# SFP.net
KiCad netlist of a schematic drawn in Altium Designer
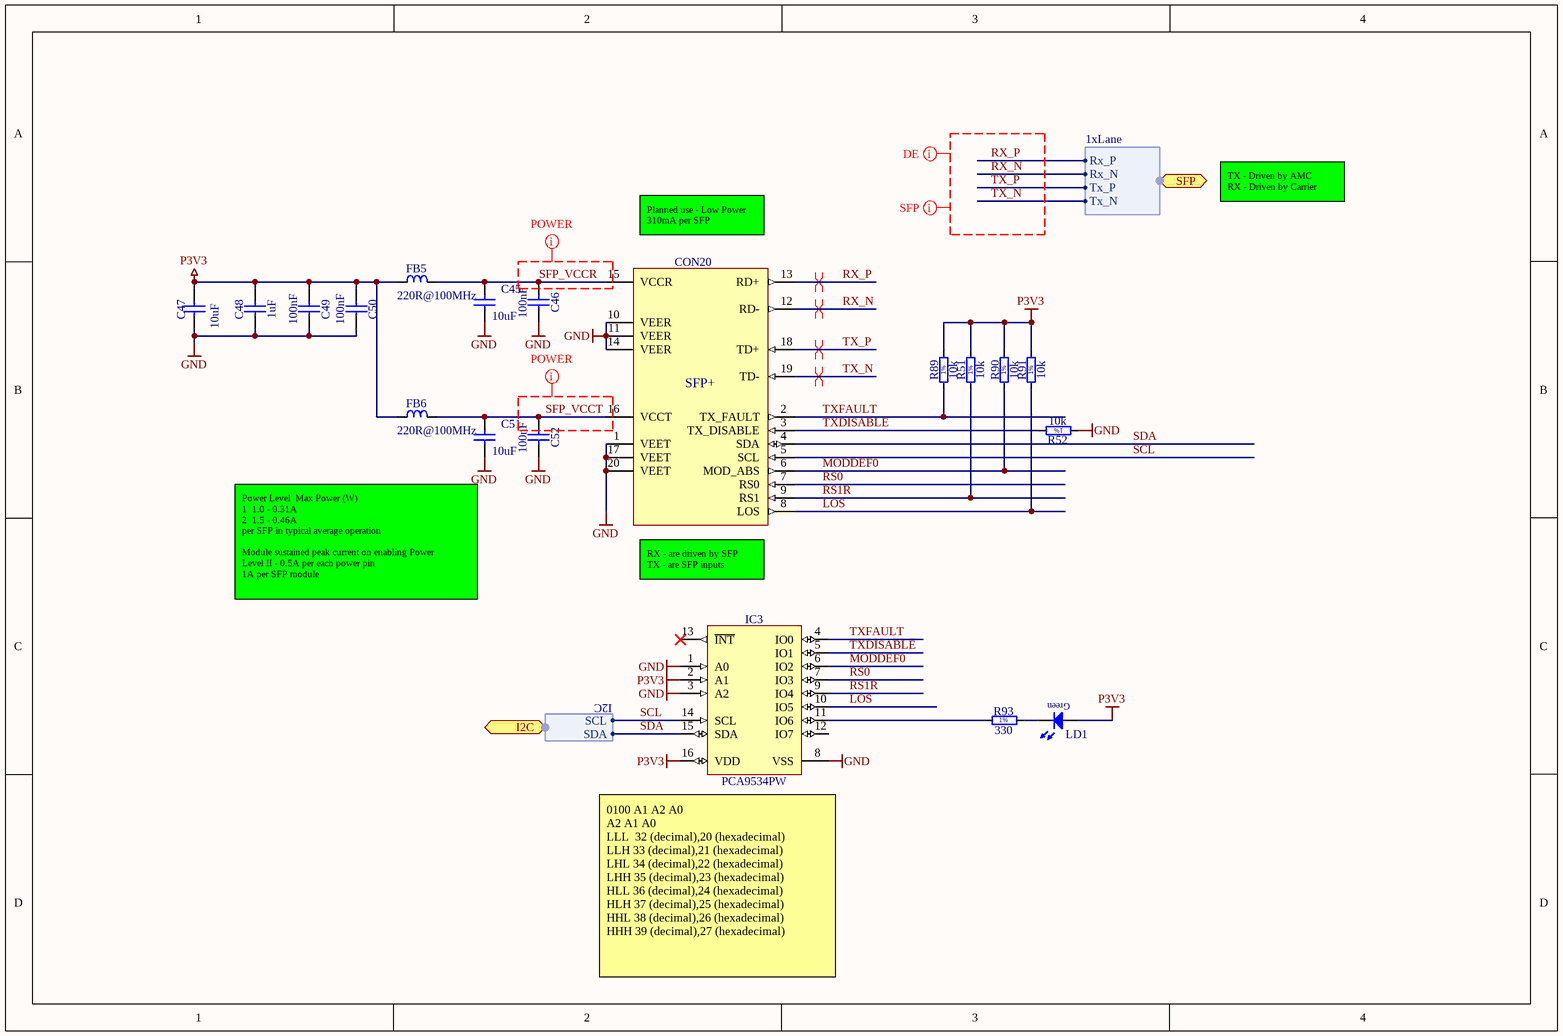
[diagram p0: SFP.SchDoc]

(export (version "E")
  (design (tool "Eeschema 10.0.6"))
  (components
    (comp (ref "C45")
      (value "10uF")
      (footprint "CAPC2012X135N")
      (description "Non-polarised capacitor")
      (fields
        (field (name "PART NUMBER") "CC0805_10UF_10V_10%_X7R")
        (field (name "VOLTAGE") "10V")
        (field (name "AUTHOR") "CERN DEM JLC")
      )
      (libsource (lib "Capacitors") (part "Capacitor - non polarized"))
    )
    (comp (ref "C46")
      (value "100nF")
      (footprint "CAPC1005X55N")
      (description "Non-polarised capacitor")
      (fields
        (field (name "PART NUMBER") "CC0402_100NF_16V_10%_X5R")
        (field (name "VOLTAGE") "16V")
        (field (name "AUTHOR") "CERN DEM JLC")
      )
      (libsource (lib "Capacitors") (part "Capacitor - non polarized"))
    )
    (comp (ref "C47")
      (value "10uF")
      (footprint "CAPC2012X135N")
      (description "Non-polarised capacitor")
      (fields
        (field (name "PART NUMBER") "CC0805_10UF_10V_10%_X7R")
        (field (name "VOLTAGE") "10V")
        (field (name "AUTHOR") "CERN DEM JLC")
      )
      (libsource (lib "Capacitors") (part "Capacitor - non polarized"))
    )
    (comp (ref "C48")
      (value "1uF")
      (footprint "CAPC1608X87N")
      (description "Non-polarised capacitor")
      (fields
        (field (name "PART NUMBER") "CC0603_1UF_25V_10%_X7R")
        (field (name "VOLTAGE") "25V")
        (field (name "AUTHOR") "CERN DEM JLC")
      )
      (libsource (lib "Capacitors") (part "Capacitor - non polarized"))
    )
    (comp (ref "C49")
      (value "100nF")
      (footprint "CAPC1005X55N")
      (description "Non-polarised capacitor")
      (fields
        (field (name "PART NUMBER") "CC0402_100NF_16V_10%_X5R")
        (field (name "VOLTAGE") "16V")
        (field (name "AUTHOR") "CERN DEM JLC")
      )
      (libsource (lib "Capacitors") (part "Capacitor - non polarized"))
    )
    (comp (ref "C50")
      (value "100nF")
      (footprint "CAPC1005X55N")
      (description "Non-polarised capacitor")
      (fields
        (field (name "PART NUMBER") "CC0402_100NF_16V_10%_X5R")
        (field (name "VOLTAGE") "16V")
        (field (name "AUTHOR") "CERN DEM JLC")
      )
      (libsource (lib "Capacitors") (part "Capacitor - non polarized"))
    )
    (comp (ref "C51")
      (value "10uF")
      (footprint "CAPC2012X135N")
      (description "Non-polarised capacitor")
      (fields
        (field (name "PART NUMBER") "CC0805_10UF_10V_10%_X7R")
        (field (name "VOLTAGE") "10V")
        (field (name "AUTHOR") "CERN DEM JLC")
      )
      (libsource (lib "Capacitors") (part "Capacitor - non polarized"))
    )
    (comp (ref "C52")
      (value "100nF")
      (footprint "CAPC1005X55N")
      (description "Non-polarised capacitor")
      (fields
        (field (name "PART NUMBER") "CC0402_100NF_16V_10%_X5R")
        (field (name "VOLTAGE") "16V")
        (field (name "AUTHOR") "CERN DEM JLC")
      )
      (libsource (lib "Capacitors") (part "Capacitor - non polarized"))
    )
    (comp (ref "CON20")
      (value "1888247-1")
      (footprint "TYCO_1888247-1")
      (description "20 Position SFP+ Connector (Small Form-factor Pluggable)")
      (fields
        (field (name "PART NUMBER") "TYCO_1888247-1")
        (field (name "MANUFACTURER") "TYCO ELECTRONICS")
        (field (name "AUTHOR") "CERN DEM JLC")
      )
      (libsource (lib "Connectors") (part "SFP+x1"))
    )
    (comp (ref "FB5")
      (value "220R@100MHz")
      (footprint "INDC2012X105N")
      (description "Inductor")
      (fields
        (field (name "PART NUMBER") "IND0805_MURATA_BLM21PG221SN1D")
        (field (name "POWER") "2A")
        (field (name "AUTHOR") "CERN DEM JLC")
      )
      (libsource (lib "Inductors & Transformers") (part "Inductor"))
    )
    (comp (ref "FB6")
      (value "220R@100MHz")
      (footprint "INDC2012X105N")
      (description "Inductor")
      (fields
        (field (name "PART NUMBER") "IND0805_MURATA_BLM21PG221SN1D")
        (field (name "POWER") "2A")
        (field (name "AUTHOR") "CERN DEM JLC")
      )
      (libsource (lib "Inductors & Transformers") (part "Inductor"))
    )
    (comp (ref "IC3")
      (value "PCA9534PW")
      (footprint "SOP65P640X110-16N")
      (description "8-Bit I2C-Bus and SMBus Low Power I/O Port with Interrupt")
      (fields (field (name "MANUFACTURER") "ANALOG DEVICES") (field (name "AUTHOR") "CERN DEM JLC"))
      (libsource (lib "ICs And Semiconductors") (part "PCA9534PW"))
    )
    (comp (ref "LD1")
      (value "LED_AVAGO_HSME-C120")
      (footprint "LED_AVAGO_HSME-C120")
      (description "LED Green 1C 2A")
      (fields
        (field (name "MANUFACTURER") "AVAGO TECHNOLOGIES")
        (field (name "MANUFACTURER PART NUMBER") "HSME-C120")
        (field (name "AUTHOR") "CERN DEM JMW")
      )
      (libsource (lib "ICs And Semiconductors") (part "LED Green 1C 2A"))
    )
    (comp (ref "R51")
      (value "10k")
      (footprint "RESC1005X40N")
      (description "Resistor - 1%")
      (fields
        (field (name "PART NUMBER") "R0402_10K_1%_0.0625W_100PPM")
        (field (name "POWER") "0.0625W")
        (field (name "AUTHOR") "CERN DEM JLC")
      )
      (libsource (lib "Resistors") (part "Resistor - 1%"))
    )
    (comp (ref "R52")
      (value "10k")
      (footprint "RESC1005X40N")
      (description "Resistor - 1%")
      (fields
        (field (name "PART NUMBER") "R0402_10K_1%_0.0625W_100PPM")
        (field (name "POWER") "0.0625W")
        (field (name "AUTHOR") "CERN DEM JLC")
      )
      (libsource (lib "Resistors") (part "Resistor - 1%"))
    )
    (comp (ref "R89")
      (value "10k")
      (footprint "RESC1005X40N")
      (description "Resistor - 1%")
      (fields
        (field (name "PART NUMBER") "R0402_10K_1%_0.0625W_100PPM")
        (field (name "POWER") "0.0625W")
        (field (name "AUTHOR") "CERN DEM JLC")
      )
      (libsource (lib "Resistors") (part "Resistor - 1%"))
    )
    (comp (ref "R90")
      (value "10k")
      (footprint "RESC1005X40N")
      (description "Resistor - 1%")
      (fields
        (field (name "PART NUMBER") "R0402_10K_1%_0.0625W_100PPM")
        (field (name "POWER") "0.0625W")
        (field (name "AUTHOR") "CERN DEM JLC")
      )
      (libsource (lib "Resistors") (part "Resistor - 1%"))
    )
    (comp (ref "R91")
      (value "10k")
      (footprint "RESC1005X40N")
      (description "Resistor - 1%")
      (fields
        (field (name "PART NUMBER") "R0402_10K_1%_0.0625W_100PPM")
        (field (name "POWER") "0.0625W")
        (field (name "AUTHOR") "CERN DEM JLC")
      )
      (libsource (lib "Resistors") (part "Resistor - 1%"))
    )
    (comp (ref "R93")
      (value "330")
      (footprint "RESC1608X55N")
      (description "Resistor - 1%")
      (fields
        (field (name "PART NUMBER") "R0603_330R_1%_0.1W_100PPM")
        (field (name "POWER") "0.1W")
        (field (name "AUTHOR") "CERN DEM JLC")
      )
      (libsource (lib "Resistors") (part "Resistor - 1%"))
    )
  )
  (nets
    (net (code "3") (name "/LOS") (class "Default")
      (node (ref "CON20") (pin "8") (pinfunction "LOS_8") (pintype "output"))
      (node (ref "IC3") (pin "10") (pinfunction "IO5_10") (pintype "bidirectional"))
      (node (ref "R91") (pin "1") (pinfunction "1_1") (pintype "passive"))
    )
    (net (code "4") (name "/MODDEF0") (class "Default")
      (node (ref "CON20") (pin "6") (pinfunction "MOD_ABS_6") (pintype "output"))
      (node (ref "IC3") (pin "6") (pinfunction "IO2_6") (pintype "bidirectional"))
      (node (ref "R90") (pin "1") (pinfunction "1_1") (pintype "passive"))
    )
    (net (code "5") (name "/RS0") (class "Default")
      (node (ref "CON20") (pin "7") (pinfunction "RS0_7") (pintype "input"))
      (node (ref "IC3") (pin "7") (pinfunction "IO3_7") (pintype "bidirectional"))
    )
    (net (code "6") (name "/RS1R") (class "Default")
      (node (ref "CON20") (pin "9") (pinfunction "RS1_9") (pintype "input"))
      (node (ref "IC3") (pin "9") (pinfunction "IO4_9") (pintype "bidirectional"))
      (node (ref "R51") (pin "1") (pinfunction "1_1") (pintype "passive"))
    )
    (net (code "7") (name "/RX_N") (class "Default")
      (node (ref "CON20") (pin "12") (pinfunction "RD-_12") (pintype "output"))
    )
    (net (code "8") (name "/RX_P") (class "Default")
      (node (ref "CON20") (pin "13") (pinfunction "RD+_13") (pintype "output"))
    )
    (net (code "9") (name "/SCL") (class "Default")
      (node (ref "CON20") (pin "5") (pinfunction "SCL_5") (pintype "input"))
      (node (ref "IC3") (pin "14") (pinfunction "SCL_14") (pintype "input"))
    )
    (net (code "10") (name "/SDA") (class "Default")
      (node (ref "CON20") (pin "4") (pinfunction "SDA_4") (pintype "bidirectional"))
      (node (ref "IC3") (pin "15") (pinfunction "SDA_15") (pintype "bidirectional"))
    )
    (net (code "11") (name "/SFP_VCCR") (class "Default")
      (node (ref "C45") (pin "1") (pinfunction "1_1") (pintype "passive"))
      (node (ref "C46") (pin "1") (pinfunction "1_1") (pintype "passive"))
      (node (ref "CON20") (pin "15") (pinfunction "VCCR_15") (pintype "power_in"))
      (node (ref "FB5") (pin "2") (pinfunction "2_2") (pintype "passive"))
    )
    (net (code "12") (name "/SFP_VCCT") (class "Default")
      (node (ref "C51") (pin "1") (pinfunction "1_1") (pintype "passive"))
      (node (ref "C52") (pin "1") (pinfunction "1_1") (pintype "passive"))
      (node (ref "CON20") (pin "16") (pinfunction "VCCT_16") (pintype "power_in"))
      (node (ref "FB6") (pin "2") (pinfunction "2_2") (pintype "passive"))
    )
    (net (code "13") (name "/TXDISABLE") (class "Default")
      (node (ref "CON20") (pin "3") (pinfunction "TX_DISABLE_3") (pintype "input"))
      (node (ref "IC3") (pin "5") (pinfunction "IO1_5") (pintype "bidirectional"))
      (node (ref "R52") (pin "2") (pinfunction "2_2") (pintype "passive"))
    )
    (net (code "14") (name "/TXFAULT") (class "Default")
      (node (ref "CON20") (pin "2") (pinfunction "TX_FAULT_2") (pintype "output"))
      (node (ref "IC3") (pin "4") (pinfunction "IO0_4") (pintype "bidirectional"))
      (node (ref "R89") (pin "1") (pinfunction "1_1") (pintype "passive"))
    )
    (net (code "15") (name "/TX_N") (class "Default")
      (node (ref "CON20") (pin "19") (pinfunction "TD-_19") (pintype "input"))
    )
    (net (code "16") (name "/TX_P") (class "Default")
      (node (ref "CON20") (pin "18") (pinfunction "TD+_18") (pintype "input"))
    )
    (net (code "19") (name "GND") (class "Default")
      (node (ref "C45") (pin "2") (pinfunction "2_2") (pintype "passive"))
      (node (ref "C46") (pin "2") (pinfunction "2_2") (pintype "passive"))
      (node (ref "C47") (pin "2") (pinfunction "2_2") (pintype "passive"))
      (node (ref "C48") (pin "1") (pinfunction "1_1") (pintype "passive"))
      (node (ref "C49") (pin "2") (pinfunction "2_2") (pintype "passive"))
      (node (ref "C50") (pin "2") (pinfunction "2_2") (pintype "passive"))
      (node (ref "C51") (pin "2") (pinfunction "2_2") (pintype "passive"))
      (node (ref "C52") (pin "2") (pinfunction "2_2") (pintype "passive"))
      (node (ref "CON20") (pin "1") (pinfunction "VEET_1") (pintype "power_in"))
      (node (ref "CON20") (pin "10") (pinfunction "VEER_10") (pintype "power_in"))
      (node (ref "CON20") (pin "11") (pinfunction "VEER_11") (pintype "power_in"))
      (node (ref "CON20") (pin "14") (pinfunction "VEER_14") (pintype "power_in"))
      (node (ref "CON20") (pin "17") (pinfunction "VEET_17") (pintype "power_in"))
      (node (ref "CON20") (pin "20") (pinfunction "VEET_20") (pintype "power_in"))
      (node (ref "IC3") (pin "1") (pinfunction "A0_1") (pintype "input"))
      (node (ref "IC3") (pin "3") (pinfunction "A2_3") (pintype "input"))
      (node (ref "IC3") (pin "8") (pinfunction "VSS_8") (pintype "power_in"))
      (node (ref "R52") (pin "1") (pinfunction "1_1") (pintype "passive"))
    )
    (net (code "20") (name "Net-(IC3-IO6)") (class "Default")
      (node (ref "IC3") (pin "11") (pinfunction "IO6_11") (pintype "bidirectional"))
      (node (ref "R93") (pin "1") (pinfunction "1_1") (pintype "passive"))
    )
    (net (code "21") (name "Net-(LD1-C)") (class "Default")
      (node (ref "LD1") (pin "1") (pinfunction "C_1") (pintype "passive"))
      (node (ref "R93") (pin "2") (pinfunction "2_2") (pintype "passive"))
    )
    (net (code "22") (name "P3V3") (class "Default")
      (node (ref "C47") (pin "1") (pinfunction "1_1") (pintype "passive"))
      (node (ref "C48") (pin "2") (pinfunction "2_2") (pintype "passive"))
      (node (ref "C49") (pin "1") (pinfunction "1_1") (pintype "passive"))
      (node (ref "C50") (pin "1") (pinfunction "1_1") (pintype "passive"))
      (node (ref "FB5") (pin "1") (pinfunction "1_1") (pintype "passive"))
      (node (ref "FB6") (pin "1") (pinfunction "1_1") (pintype "passive"))
      (node (ref "IC3") (pin "16") (pinfunction "VDD_16") (pintype "bidirectional"))
      (node (ref "IC3") (pin "2") (pinfunction "A1_2") (pintype "input"))
      (node (ref "LD1") (pin "2") (pinfunction "A_2") (pintype "passive"))
      (node (ref "R51") (pin "2") (pinfunction "2_2") (pintype "passive"))
      (node (ref "R89") (pin "2") (pinfunction "2_2") (pintype "passive"))
      (node (ref "R90") (pin "2") (pinfunction "2_2") (pintype "passive"))
      (node (ref "R91") (pin "2") (pinfunction "2_2") (pintype "passive"))
    )
    (net (code "23") (name "unconnected-(IC3-IO7-Pad12)") (class "Default")
      (node (ref "IC3") (pin "12") (pinfunction "IO7_12") (pintype "bidirectional"))
    )
    (net (code "24") (name "unconnected-(IC3-~{INT}-Pad13)") (class "Default")
      (node (ref "IC3") (pin "13") (pinfunction "~{INT}_13") (pintype "output+no_connect"))
    )
  )
)
